# AtMega88.net
KiCad netlist of a schematic drawn in EAGLE
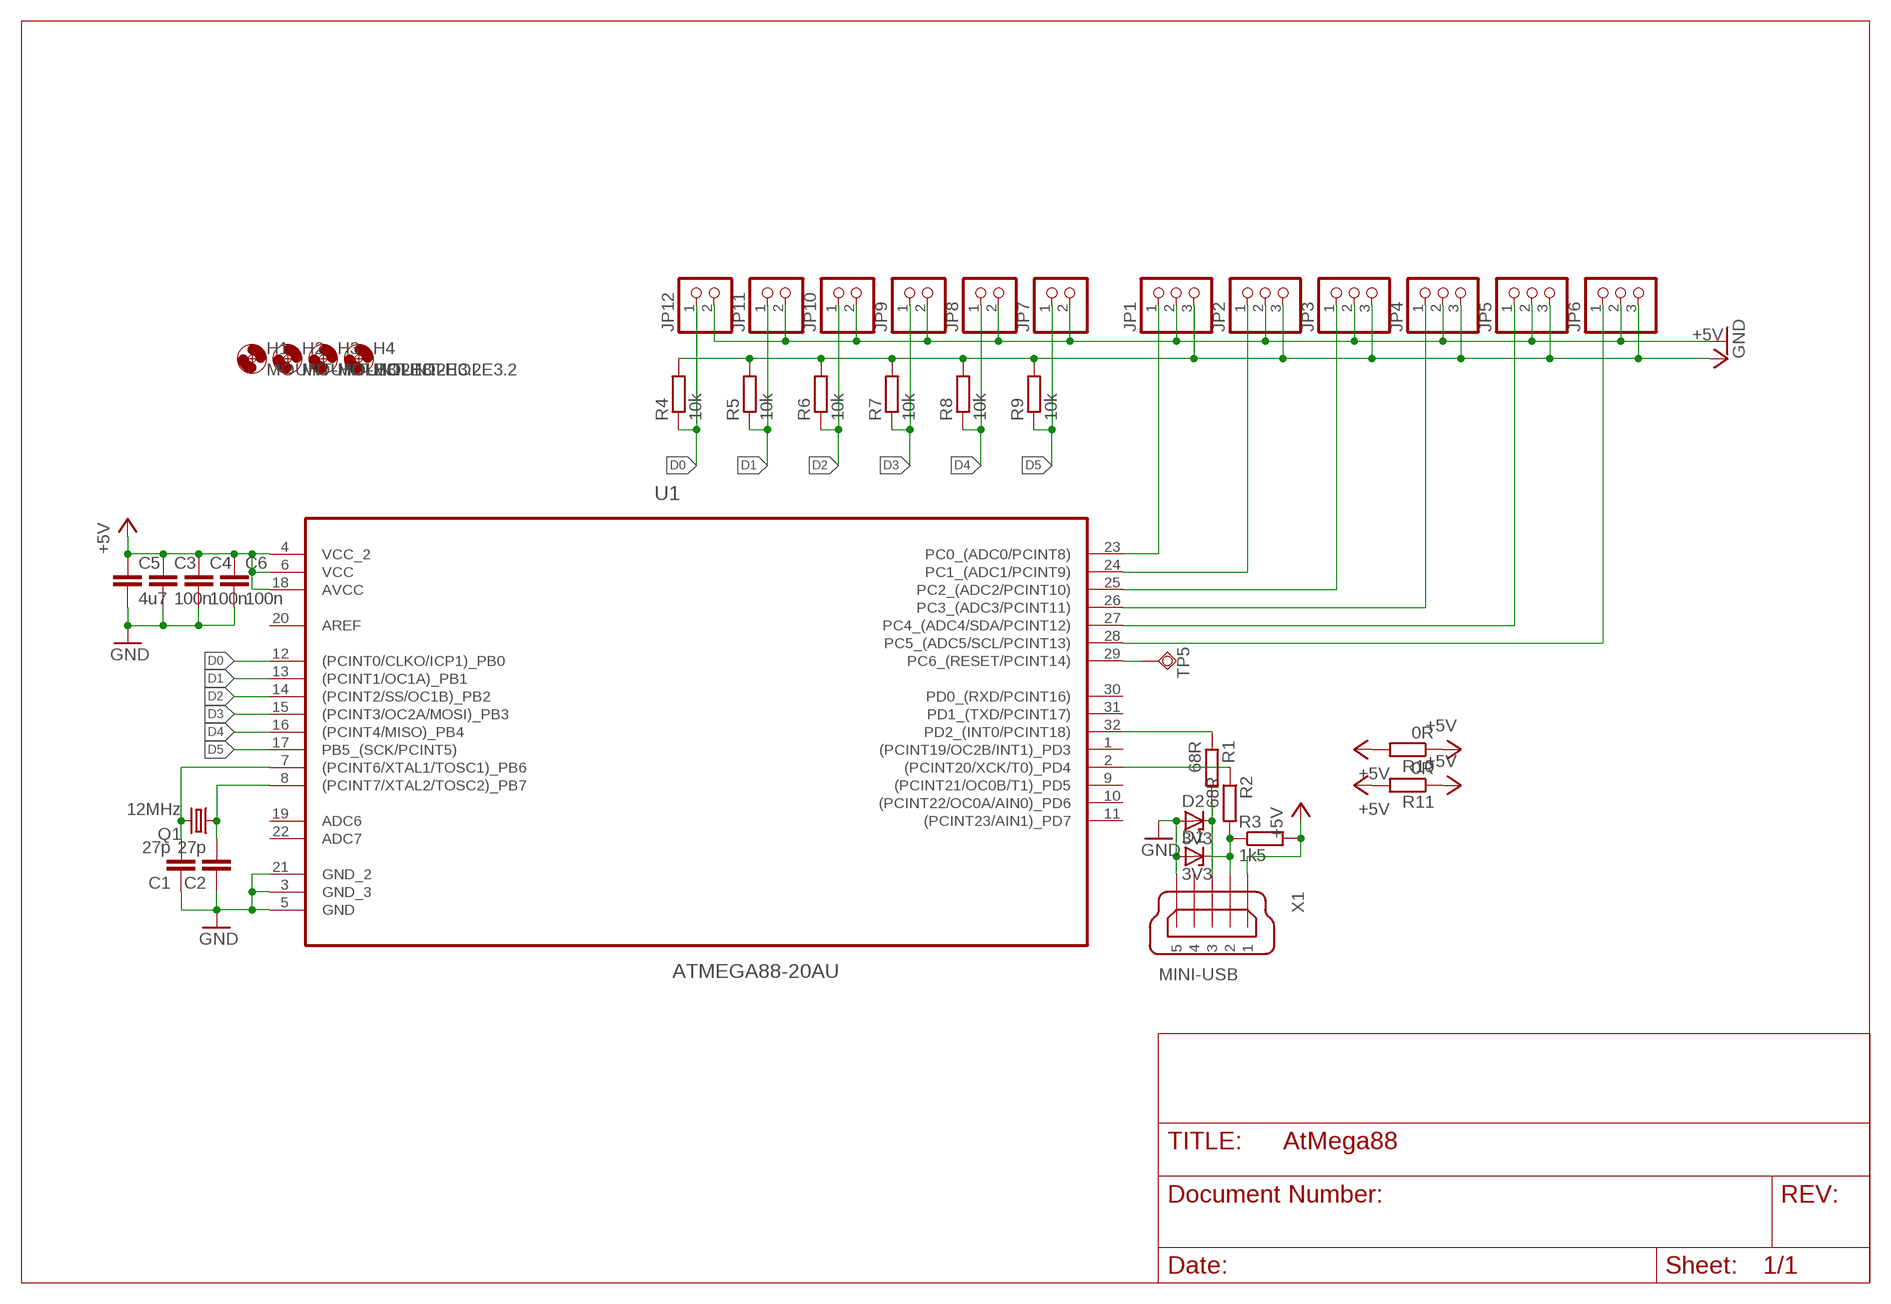
[diagram p0: schematic, sheet 1]

(export (version "E")
  (design (tool "Eeschema 10.0.6"))
  (components
    (comp (ref "C1")
      (value "27p")
      (footprint "eagle-import:C0805")
      (libsource (lib "eagle-import") (part "C-EUC0805"))
    )
    (comp (ref "C2")
      (value "27p")
      (footprint "eagle-import:C0805")
      (libsource (lib "eagle-import") (part "C-EUC0805"))
    )
    (comp (ref "C3")
      (value "100n")
      (footprint "eagle-import:C0805")
      (libsource (lib "eagle-import") (part "C-EUC0805"))
    )
    (comp (ref "C4")
      (value "100n")
      (footprint "eagle-import:C0805")
      (libsource (lib "eagle-import") (part "C-EUC0805"))
    )
    (comp (ref "C5")
      (value "4u7")
      (footprint "eagle-import:C0805")
      (libsource (lib "eagle-import") (part "C-EUC0805"))
    )
    (comp (ref "C6")
      (value "100n")
      (footprint "eagle-import:C0805")
      (libsource (lib "eagle-import") (part "C-EUC0805"))
    )
    (comp (ref "D1")
      (value "3V3")
      (footprint "eagle-import:SOT23")
      (libsource (lib "eagle-import") (part "ZENER-DIODESOT23"))
    )
    (comp (ref "D2")
      (value "3V3")
      (footprint "eagle-import:SOT23")
      (libsource (lib "eagle-import") (part "ZENER-DIODESOT23"))
    )
    (comp (ref "H1")
      (value "MOUNT-HOLE3.2")
      (footprint "eagle-import:3,2")
      (libsource (lib "eagle-import") (part "MOUNT-HOLE3.2"))
    )
    (comp (ref "H2")
      (value "MOUNT-HOLE3.2")
      (footprint "eagle-import:3,2")
      (libsource (lib "eagle-import") (part "MOUNT-HOLE3.2"))
    )
    (comp (ref "H3")
      (value "MOUNT-HOLE3.2")
      (footprint "eagle-import:3,2")
      (libsource (lib "eagle-import") (part "MOUNT-HOLE3.2"))
    )
    (comp (ref "H4")
      (value "MOUNT-HOLE3.2")
      (footprint "eagle-import:3,2")
      (libsource (lib "eagle-import") (part "MOUNT-HOLE3.2"))
    )
    (comp (ref "JP1")
      (value "PINHD-1X3")
      (footprint "eagle-import:1X03")
      (libsource (lib "eagle-import") (part "PINHD-1X3"))
    )
    (comp (ref "JP2")
      (value "PINHD-1X3")
      (footprint "eagle-import:1X03")
      (libsource (lib "eagle-import") (part "PINHD-1X3"))
    )
    (comp (ref "JP3")
      (value "PINHD-1X3")
      (footprint "eagle-import:1X03")
      (libsource (lib "eagle-import") (part "PINHD-1X3"))
    )
    (comp (ref "JP4")
      (value "PINHD-1X3")
      (footprint "eagle-import:1X03")
      (libsource (lib "eagle-import") (part "PINHD-1X3"))
    )
    (comp (ref "JP5")
      (value "PINHD-1X3")
      (footprint "eagle-import:1X03")
      (libsource (lib "eagle-import") (part "PINHD-1X3"))
    )
    (comp (ref "JP6")
      (value "PINHD-1X3")
      (footprint "eagle-import:1X03")
      (libsource (lib "eagle-import") (part "PINHD-1X3"))
    )
    (comp (ref "JP7")
      (value "PINHD-1X2")
      (footprint "eagle-import:1X02")
      (libsource (lib "eagle-import") (part "PINHD-1X2"))
    )
    (comp (ref "JP8")
      (value "PINHD-1X2")
      (footprint "eagle-import:1X02")
      (libsource (lib "eagle-import") (part "PINHD-1X2"))
    )
    (comp (ref "JP9")
      (value "PINHD-1X2")
      (footprint "eagle-import:1X02")
      (libsource (lib "eagle-import") (part "PINHD-1X2"))
    )
    (comp (ref "JP10")
      (value "PINHD-1X2")
      (footprint "eagle-import:1X02")
      (libsource (lib "eagle-import") (part "PINHD-1X2"))
    )
    (comp (ref "JP11")
      (value "PINHD-1X2")
      (footprint "eagle-import:1X02")
      (libsource (lib "eagle-import") (part "PINHD-1X2"))
    )
    (comp (ref "JP12")
      (value "PINHD-1X2")
      (footprint "eagle-import:1X02")
      (libsource (lib "eagle-import") (part "PINHD-1X2"))
    )
    (comp (ref "Q1")
      (value "12MHz")
      (footprint "eagle-import:CSM-7X-DU")
      (libsource (lib "eagle-import") (part "CSM-7X-DU"))
    )
    (comp (ref "R1")
      (value "68R")
      (footprint "eagle-import:R1206")
      (libsource (lib "eagle-import") (part "R-EU_R1206"))
    )
    (comp (ref "R2")
      (value "68R")
      (footprint "eagle-import:R1206")
      (libsource (lib "eagle-import") (part "R-EU_R1206"))
    )
    (comp (ref "R3")
      (value "1k5")
      (footprint "eagle-import:R1206")
      (libsource (lib "eagle-import") (part "R-EU_R1206"))
    )
    (comp (ref "R4")
      (value "10k")
      (footprint "eagle-import:R1206")
      (libsource (lib "eagle-import") (part "R-EU_R1206"))
    )
    (comp (ref "R5")
      (value "10k")
      (footprint "eagle-import:R1206")
      (libsource (lib "eagle-import") (part "R-EU_R1206"))
    )
    (comp (ref "R6")
      (value "10k")
      (footprint "eagle-import:R1206")
      (libsource (lib "eagle-import") (part "R-EU_R1206"))
    )
    (comp (ref "R7")
      (value "10k")
      (footprint "eagle-import:R1206")
      (libsource (lib "eagle-import") (part "R-EU_R1206"))
    )
    (comp (ref "R8")
      (value "10k")
      (footprint "eagle-import:R1206")
      (libsource (lib "eagle-import") (part "R-EU_R1206"))
    )
    (comp (ref "R9")
      (value "10k")
      (footprint "eagle-import:R1206")
      (libsource (lib "eagle-import") (part "R-EU_R1206"))
    )
    (comp (ref "R10")
      (value "0R")
      (footprint "eagle-import:R1206")
      (libsource (lib "eagle-import") (part "R-EU_R1206"))
    )
    (comp (ref "R11")
      (value "0R")
      (footprint "eagle-import:R1206")
      (libsource (lib "eagle-import") (part "R-EU_R1206"))
    )
    (comp (ref "TP5")
      (value "TPSQTP20SQ")
      (footprint "eagle-import:TP20SQ")
      (libsource (lib "eagle-import") (part "TPSQTP20SQ"))
    )
    (comp (ref "U1")
      (value "ATMEGA88-20AU")
      (footprint "eagle-import:QFP80P900X900X120-32N")
      (libsource (lib "eagle-import") (part "ATMEGA88-20AU"))
    )
    (comp (ref "X1")
      (value "MINI-USB")
      (footprint "eagle-import:UX60A-MB-5ST")
      (libsource (lib "eagle-import") (part "MINI-USB-UX60A-MB-5ST"))
    )
  )
  (nets
    (net (code "1") (name "+5V") (class "Default")
      (node (ref "C3") (pin "1") (pinfunction "1_1") (pintype "passive"))
      (node (ref "C4") (pin "1") (pinfunction "1_1") (pintype "passive"))
      (node (ref "C5") (pin "1") (pinfunction "1_1") (pintype "passive"))
      (node (ref "C6") (pin "1") (pinfunction "1_1") (pintype "passive"))
      (node (ref "JP1") (pin "3") (pinfunction "3_3") (pintype "passive"))
      (node (ref "JP2") (pin "3") (pinfunction "3_3") (pintype "passive"))
      (node (ref "JP3") (pin "3") (pinfunction "3_3") (pintype "passive"))
      (node (ref "JP4") (pin "3") (pinfunction "3_3") (pintype "passive"))
      (node (ref "JP5") (pin "3") (pinfunction "3_3") (pintype "passive"))
      (node (ref "JP6") (pin "3") (pinfunction "3_3") (pintype "passive"))
      (node (ref "R10") (pin "1") (pinfunction "1_1") (pintype "passive"))
      (node (ref "R10") (pin "2") (pinfunction "2_2") (pintype "passive"))
      (node (ref "R11") (pin "1") (pinfunction "1_1") (pintype "passive"))
      (node (ref "R11") (pin "2") (pinfunction "2_2") (pintype "passive"))
      (node (ref "R3") (pin "2") (pinfunction "2_2") (pintype "passive"))
      (node (ref "R4") (pin "2") (pinfunction "2_2") (pintype "passive"))
      (node (ref "R5") (pin "2") (pinfunction "2_2") (pintype "passive"))
      (node (ref "R6") (pin "2") (pinfunction "2_2") (pintype "passive"))
      (node (ref "R7") (pin "2") (pinfunction "2_2") (pintype "passive"))
      (node (ref "R8") (pin "2") (pinfunction "2_2") (pintype "passive"))
      (node (ref "R9") (pin "2") (pinfunction "2_2") (pintype "passive"))
      (node (ref "U1") (pin "18") (pinfunction "AVCC_18") (pintype "power_in"))
      (node (ref "U1") (pin "4") (pinfunction "VCC_2_4") (pintype "power_in"))
      (node (ref "U1") (pin "6") (pinfunction "VCC_6") (pintype "power_in"))
      (node (ref "X1") (pin "1") (pinfunction "1_1") (pintype "input"))
    )
    (net (code "2") (name "D0") (class "Default")
      (node (ref "JP12") (pin "1") (pinfunction "1_1") (pintype "passive"))
      (node (ref "R4") (pin "1") (pinfunction "1_1") (pintype "passive"))
      (node (ref "U1") (pin "12") (pinfunction "(PCINT0/CLKO/ICP1)_PB0_12") (pintype "bidirectional"))
    )
    (net (code "3") (name "D1") (class "Default")
      (node (ref "JP11") (pin "1") (pinfunction "1_1") (pintype "passive"))
      (node (ref "R5") (pin "1") (pinfunction "1_1") (pintype "passive"))
      (node (ref "U1") (pin "13") (pinfunction "(PCINT1/OC1A)_PB1_13") (pintype "bidirectional"))
    )
    (net (code "4") (name "D2") (class "Default")
      (node (ref "JP10") (pin "1") (pinfunction "1_1") (pintype "passive"))
      (node (ref "R6") (pin "1") (pinfunction "1_1") (pintype "passive"))
      (node (ref "U1") (pin "14") (pinfunction "(PCINT2/SS/OC1B)_PB2_14") (pintype "bidirectional"))
    )
    (net (code "5") (name "D3") (class "Default")
      (node (ref "JP9") (pin "1") (pinfunction "1_1") (pintype "passive"))
      (node (ref "R7") (pin "1") (pinfunction "1_1") (pintype "passive"))
      (node (ref "U1") (pin "15") (pinfunction "(PCINT3/OC2A/MOSI)_PB3_15") (pintype "bidirectional"))
    )
    (net (code "6") (name "D4") (class "Default")
      (node (ref "JP8") (pin "1") (pinfunction "1_1") (pintype "passive"))
      (node (ref "R8") (pin "1") (pinfunction "1_1") (pintype "passive"))
      (node (ref "U1") (pin "16") (pinfunction "(PCINT4/MISO)_PB4_16") (pintype "bidirectional"))
    )
    (net (code "7") (name "D5") (class "Default")
      (node (ref "JP7") (pin "1") (pinfunction "1_1") (pintype "passive"))
      (node (ref "R9") (pin "1") (pinfunction "1_1") (pintype "passive"))
      (node (ref "U1") (pin "17") (pinfunction "PB5_(SCK/PCINT5)_17") (pintype "bidirectional"))
    )
    (net (code "8") (name "GND") (class "Default")
      (node (ref "C1") (pin "1") (pinfunction "1_1") (pintype "passive"))
      (node (ref "C2") (pin "1") (pinfunction "1_1") (pintype "passive"))
      (node (ref "C3") (pin "2") (pinfunction "2_2") (pintype "passive"))
      (node (ref "C4") (pin "2") (pinfunction "2_2") (pintype "passive"))
      (node (ref "C5") (pin "2") (pinfunction "2_2") (pintype "passive"))
      (node (ref "C6") (pin "2") (pinfunction "2_2") (pintype "passive"))
      (node (ref "D1") (pin "1") (pinfunction "A_1") (pintype "passive"))
      (node (ref "D2") (pin "1") (pinfunction "A_1") (pintype "passive"))
      (node (ref "JP1") (pin "2") (pinfunction "2_2") (pintype "passive"))
      (node (ref "JP10") (pin "2") (pinfunction "2_2") (pintype "passive"))
      (node (ref "JP11") (pin "2") (pinfunction "2_2") (pintype "passive"))
      (node (ref "JP12") (pin "2") (pinfunction "2_2") (pintype "passive"))
      (node (ref "JP2") (pin "2") (pinfunction "2_2") (pintype "passive"))
      (node (ref "JP3") (pin "2") (pinfunction "2_2") (pintype "passive"))
      (node (ref "JP4") (pin "2") (pinfunction "2_2") (pintype "passive"))
      (node (ref "JP5") (pin "2") (pinfunction "2_2") (pintype "passive"))
      (node (ref "JP6") (pin "2") (pinfunction "2_2") (pintype "passive"))
      (node (ref "JP7") (pin "2") (pinfunction "2_2") (pintype "passive"))
      (node (ref "JP8") (pin "2") (pinfunction "2_2") (pintype "passive"))
      (node (ref "JP9") (pin "2") (pinfunction "2_2") (pintype "passive"))
      (node (ref "U1") (pin "21") (pinfunction "GND_2_21") (pintype "passive"))
      (node (ref "U1") (pin "3") (pinfunction "GND_3_3") (pintype "passive"))
      (node (ref "U1") (pin "5") (pinfunction "GND_5") (pintype "passive"))
      (node (ref "X1") (pin "5") (pinfunction "5_5") (pintype "input"))
    )
    (net (code "9") (name "Net-(D1-C)") (class "Default")
      (node (ref "D1") (pin "3") (pinfunction "C_3") (pintype "passive"))
      (node (ref "R2") (pin "2") (pinfunction "2_2") (pintype "passive"))
      (node (ref "R3") (pin "1") (pinfunction "1_1") (pintype "passive"))
      (node (ref "X1") (pin "2") (pinfunction "2_2") (pintype "input"))
    )
    (net (code "10") (name "Net-(D2-C)") (class "Default")
      (node (ref "D2") (pin "3") (pinfunction "C_3") (pintype "passive"))
      (node (ref "R1") (pin "2") (pinfunction "2_2") (pintype "passive"))
      (node (ref "X1") (pin "3") (pinfunction "3_3") (pintype "input"))
    )
    (net (code "11") (name "Net-(U1-(PCINT6{slash}XTAL1{slash}TOSC1)_PB6)") (class "Default")
      (node (ref "C1") (pin "2") (pinfunction "2_2") (pintype "passive"))
      (node (ref "Q1") (pin "2") (pinfunction "2_2") (pintype "passive"))
      (node (ref "U1") (pin "7") (pinfunction "(PCINT6/XTAL1/TOSC1)_PB6_7") (pintype "bidirectional"))
    )
    (net (code "12") (name "Net-(U1-(PCINT7{slash}XTAL2{slash}TOSC2)_PB7)") (class "Default")
      (node (ref "C2") (pin "2") (pinfunction "2_2") (pintype "passive"))
      (node (ref "Q1") (pin "1") (pinfunction "1_1") (pintype "passive"))
      (node (ref "U1") (pin "8") (pinfunction "(PCINT7/XTAL2/TOSC2)_PB7_8") (pintype "bidirectional"))
    )
    (net (code "13") (name "Net-(U1-(PCINT20{slash}XCK{slash}T0)_PD4)") (class "Default")
      (node (ref "R2") (pin "1") (pinfunction "1_1") (pintype "passive"))
      (node (ref "U1") (pin "2") (pinfunction "(PCINT20/XCK/T0)_PD4_2") (pintype "bidirectional"))
    )
    (net (code "14") (name "Net-(U1-PC0_(ADC0{slash}PCINT8))") (class "Default")
      (node (ref "JP1") (pin "1") (pinfunction "1_1") (pintype "passive"))
      (node (ref "U1") (pin "23") (pinfunction "PC0_(ADC0/PCINT8)_23") (pintype "bidirectional"))
    )
    (net (code "15") (name "Net-(U1-PC1_(ADC1{slash}PCINT9))") (class "Default")
      (node (ref "JP2") (pin "1") (pinfunction "1_1") (pintype "passive"))
      (node (ref "U1") (pin "24") (pinfunction "PC1_(ADC1/PCINT9)_24") (pintype "bidirectional"))
    )
    (net (code "16") (name "Net-(U1-PC2_(ADC2{slash}PCINT10))") (class "Default")
      (node (ref "JP3") (pin "1") (pinfunction "1_1") (pintype "passive"))
      (node (ref "U1") (pin "25") (pinfunction "PC2_(ADC2/PCINT10)_25") (pintype "bidirectional"))
    )
    (net (code "17") (name "Net-(U1-PC3_(ADC3{slash}PCINT11))") (class "Default")
      (node (ref "JP4") (pin "1") (pinfunction "1_1") (pintype "passive"))
      (node (ref "U1") (pin "26") (pinfunction "PC3_(ADC3/PCINT11)_26") (pintype "bidirectional"))
    )
    (net (code "18") (name "Net-(U1-PC4_(ADC4{slash}SDA{slash}PCINT12))") (class "Default")
      (node (ref "JP5") (pin "1") (pinfunction "1_1") (pintype "passive"))
      (node (ref "U1") (pin "27") (pinfunction "PC4_(ADC4/SDA/PCINT12)_27") (pintype "bidirectional"))
    )
    (net (code "19") (name "Net-(U1-PC5_(ADC5{slash}SCL{slash}PCINT13))") (class "Default")
      (node (ref "JP6") (pin "1") (pinfunction "1_1") (pintype "passive"))
      (node (ref "U1") (pin "28") (pinfunction "PC5_(ADC5/SCL/PCINT13)_28") (pintype "bidirectional"))
    )
    (net (code "20") (name "Net-(U1-PC6_(RESET{slash}PCINT14))") (class "Default")
      (node (ref "TP5") (pin "TP") (pinfunction "TP_TP") (pintype "input"))
      (node (ref "U1") (pin "29") (pinfunction "PC6_(RESET/PCINT14)_29") (pintype "bidirectional"))
    )
    (net (code "21") (name "Net-(U1-PD2_(INT0{slash}PCINT18))") (class "Default")
      (node (ref "R1") (pin "1") (pinfunction "1_1") (pintype "passive"))
      (node (ref "U1") (pin "32") (pinfunction "PD2_(INT0/PCINT18)_32") (pintype "bidirectional"))
    )
    (net (code "22") (name "unconnected-(U1-(PCINT19{slash}OC2B{slash}INT1)_PD3-Pad1)") (class "Default")
      (node (ref "U1") (pin "1") (pinfunction "(PCINT19/OC2B/INT1)_PD3_1") (pintype "bidirectional"))
    )
    (net (code "23") (name "unconnected-(U1-(PCINT21{slash}OC0B{slash}T1)_PD5-Pad9)") (class "Default")
      (node (ref "U1") (pin "9") (pinfunction "(PCINT21/OC0B/T1)_PD5_9") (pintype "bidirectional"))
    )
    (net (code "24") (name "unconnected-(U1-(PCINT22{slash}OC0A{slash}AIN0)_PD6-Pad10)") (class "Default")
      (node (ref "U1") (pin "10") (pinfunction "(PCINT22/OC0A/AIN0)_PD6_10") (pintype "bidirectional"))
    )
    (net (code "25") (name "unconnected-(U1-(PCINT23{slash}AIN1)_PD7-Pad11)") (class "Default")
      (node (ref "U1") (pin "11") (pinfunction "(PCINT23/AIN1)_PD7_11") (pintype "bidirectional"))
    )
    (net (code "26") (name "unconnected-(U1-ADC6-Pad19)") (class "Default")
      (node (ref "U1") (pin "19") (pinfunction "ADC6_19") (pintype "input"))
    )
    (net (code "27") (name "unconnected-(U1-ADC7-Pad22)") (class "Default")
      (node (ref "U1") (pin "22") (pinfunction "ADC7_22") (pintype "input"))
    )
    (net (code "28") (name "unconnected-(U1-AREF-Pad20)") (class "Default")
      (node (ref "U1") (pin "20") (pinfunction "AREF_20") (pintype "input"))
    )
    (net (code "29") (name "unconnected-(U1-PD0_(RXD{slash}PCINT16)-Pad30)") (class "Default")
      (node (ref "U1") (pin "30") (pinfunction "PD0_(RXD/PCINT16)_30") (pintype "bidirectional"))
    )
    (net (code "30") (name "unconnected-(U1-PD1_(TXD{slash}PCINT17)-Pad31)") (class "Default")
      (node (ref "U1") (pin "31") (pinfunction "PD1_(TXD/PCINT17)_31") (pintype "bidirectional"))
    )
    (net (code "31") (name "unconnected-(X1-Pad4)") (class "Default")
      (node (ref "X1") (pin "4") (pinfunction "4_4") (pintype "input"))
    )
  )
)
